# 08_STORE_SourceRegister.net
KiCad netlist of a schematic drawn in EAGLE
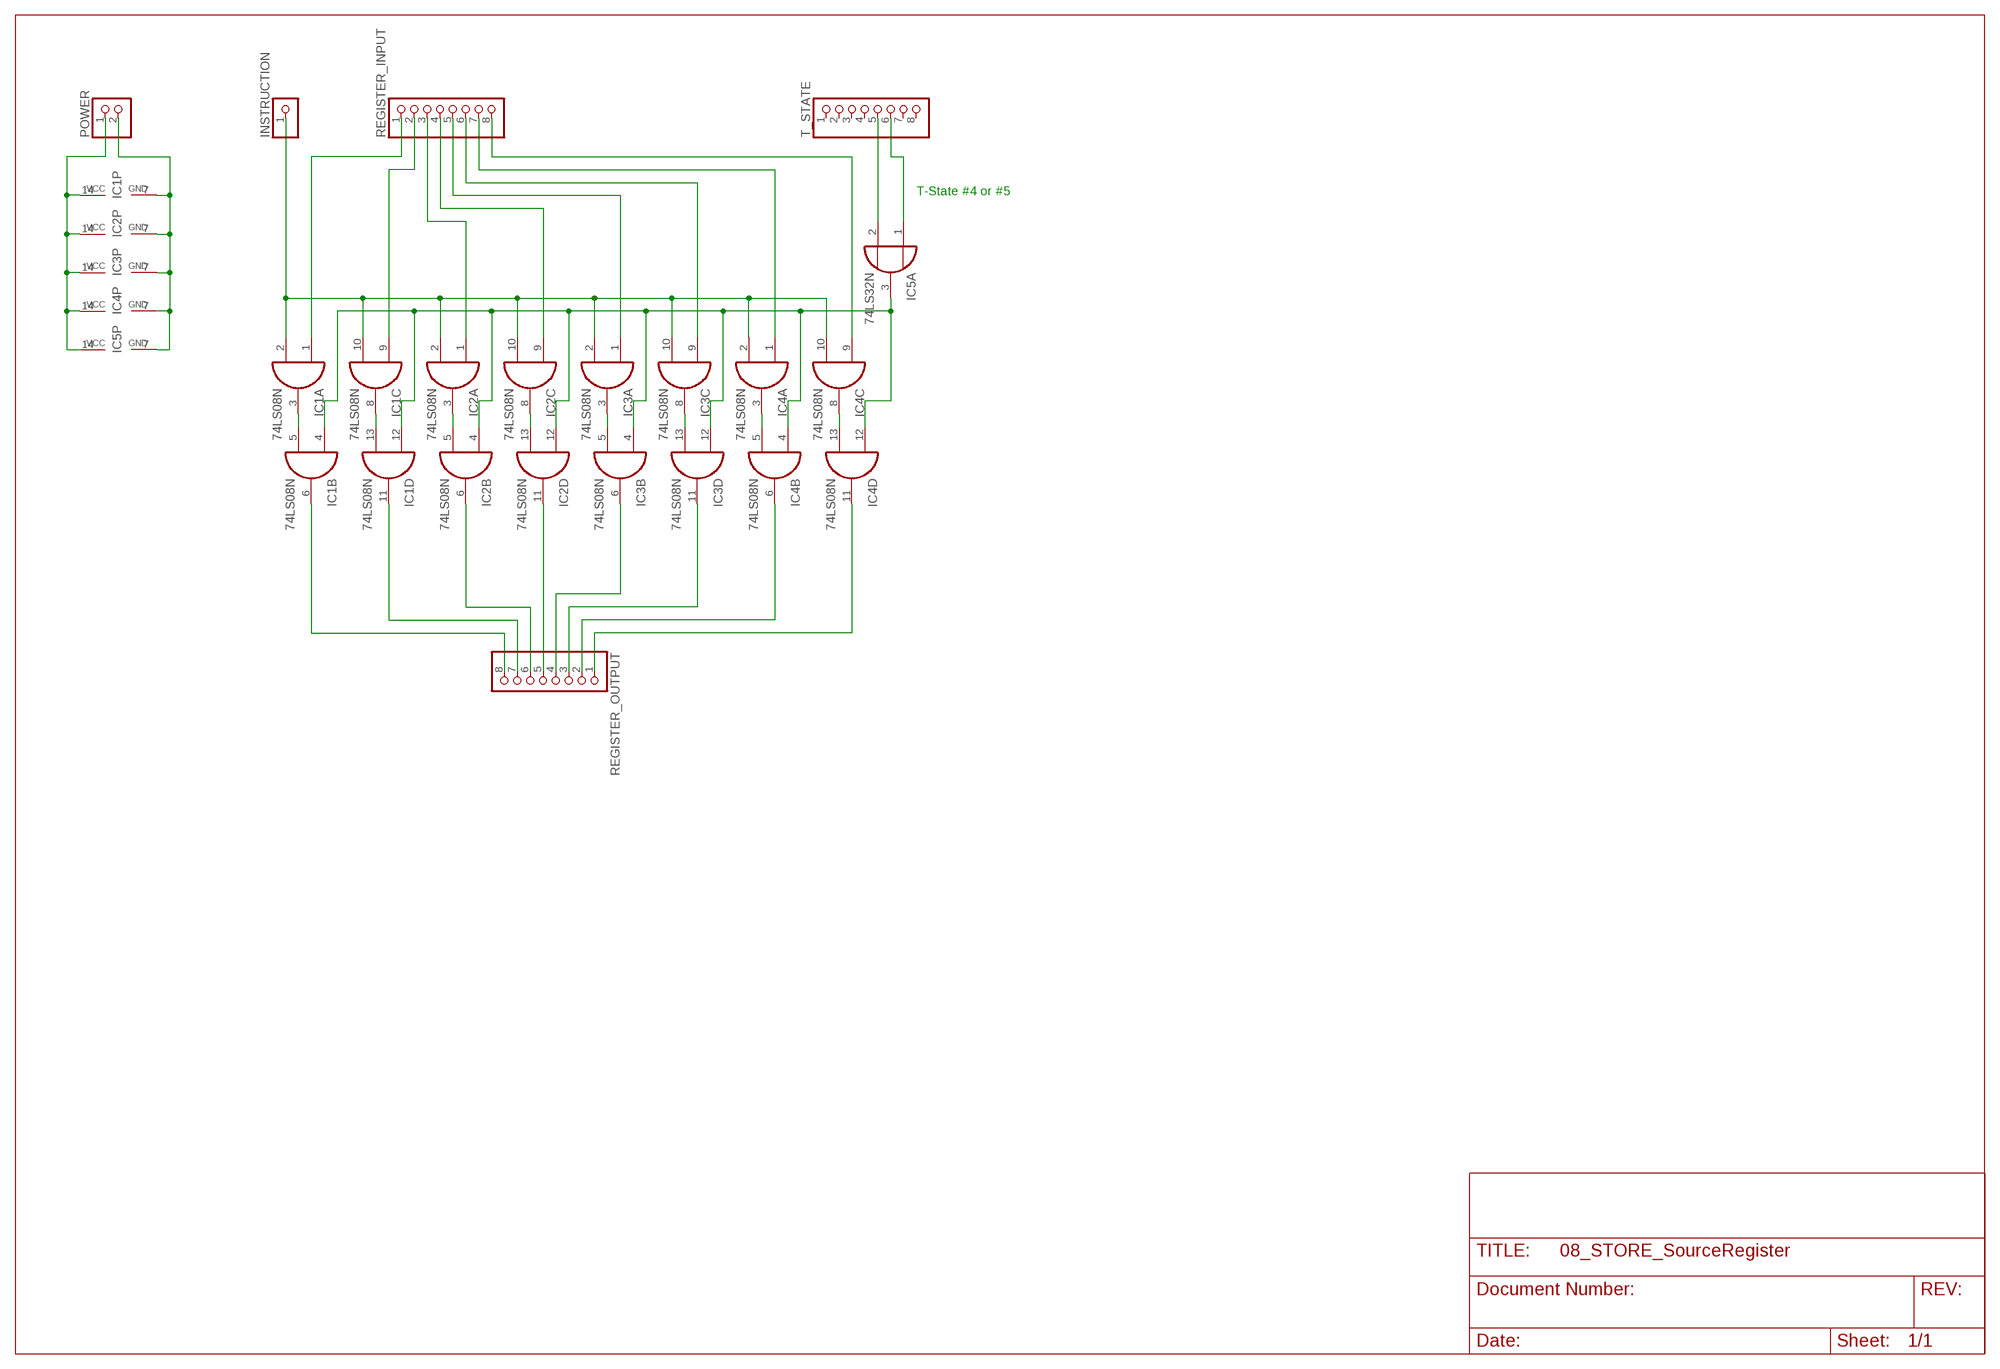
[diagram p0: schematic, sheet 1]

(export (version "E")
  (design (tool "Eeschema 10.0.6"))
  (components
    (comp (ref "IC1")
      (value "74LS08N")
      (footprint "eagle-import:DIL14")
      (libsource (lib "eagle-import") (part "7408NLS"))
    )
    (comp (ref "IC2")
      (value "74LS08N")
      (footprint "eagle-import:DIL14")
      (libsource (lib "eagle-import") (part "7408NLS"))
    )
    (comp (ref "IC3")
      (value "74LS08N")
      (footprint "eagle-import:DIL14")
      (libsource (lib "eagle-import") (part "7408NLS"))
    )
    (comp (ref "IC4")
      (value "74LS08N")
      (footprint "eagle-import:DIL14")
      (libsource (lib "eagle-import") (part "7408NLS"))
    )
    (comp (ref "IC5")
      (value "74LS32N")
      (footprint "eagle-import:DIL14")
      (libsource (lib "eagle-import") (part "7432NLS"))
    )
    (comp (ref "INSTRUCTION")
      (value "PINHD-1X1")
      (footprint "eagle-import:1X01")
      (libsource (lib "eagle-import") (part "PINHD-1X1"))
    )
    (comp (ref "POWER")
      (value "PINHD-1X2")
      (footprint "eagle-import:1X02")
      (libsource (lib "eagle-import") (part "PINHD-1X2"))
    )
    (comp (ref "REGISTER_INPUT")
      (value "PINHD-1X8")
      (footprint "eagle-import:1X08")
      (libsource (lib "eagle-import") (part "PINHD-1X8"))
    )
    (comp (ref "REGISTER_OUTPUT")
      (value "PINHD-1X8")
      (footprint "eagle-import:1X08")
      (libsource (lib "eagle-import") (part "PINHD-1X8"))
    )
    (comp (ref "T_STATE")
      (value "PINHD-1X8")
      (footprint "eagle-import:1X08")
      (libsource (lib "eagle-import") (part "PINHD-1X8"))
    )
  )
  (nets
    (net (code "1") (name "Net-(IC1A-I0)") (class "Default")
      (node (ref "IC1") (pin "1") (pinfunction "I0_1") (pintype "input"))
      (node (ref "REGISTER_INPUT") (pin "1") (pinfunction "1_1") (pintype "passive"))
    )
    (net (code "2") (name "Net-(IC1A-I1)") (class "Default")
      (node (ref "IC1") (pin "10") (pinfunction "I1_10") (pintype "input"))
      (node (ref "IC1") (pin "2") (pinfunction "I1_2") (pintype "input"))
      (node (ref "IC2") (pin "10") (pinfunction "I1_10") (pintype "input"))
      (node (ref "IC2") (pin "2") (pinfunction "I1_2") (pintype "input"))
      (node (ref "IC3") (pin "10") (pinfunction "I1_10") (pintype "input"))
      (node (ref "IC3") (pin "2") (pinfunction "I1_2") (pintype "input"))
      (node (ref "IC4") (pin "10") (pinfunction "I1_10") (pintype "input"))
      (node (ref "IC4") (pin "2") (pinfunction "I1_2") (pintype "input"))
      (node (ref "INSTRUCTION") (pin "1") (pinfunction "1_1") (pintype "passive"))
    )
    (net (code "3") (name "Net-(IC1A-O)") (class "Default")
      (node (ref "IC1") (pin "3") (pinfunction "O_3") (pintype "output"))
      (node (ref "IC1") (pin "5") (pinfunction "I1_5") (pintype "input"))
    )
    (net (code "4") (name "Net-(IC1B-I0)") (class "Default")
      (node (ref "IC1") (pin "12") (pinfunction "I0_12") (pintype "input"))
      (node (ref "IC1") (pin "4") (pinfunction "I0_4") (pintype "input"))
      (node (ref "IC2") (pin "12") (pinfunction "I0_12") (pintype "input"))
      (node (ref "IC2") (pin "4") (pinfunction "I0_4") (pintype "input"))
      (node (ref "IC3") (pin "12") (pinfunction "I0_12") (pintype "input"))
      (node (ref "IC3") (pin "4") (pinfunction "I0_4") (pintype "input"))
      (node (ref "IC4") (pin "12") (pinfunction "I0_12") (pintype "input"))
      (node (ref "IC4") (pin "4") (pinfunction "I0_4") (pintype "input"))
      (node (ref "IC5") (pin "3") (pinfunction "O_3") (pintype "output"))
    )
    (net (code "5") (name "Net-(IC1B-O)") (class "Default")
      (node (ref "IC1") (pin "6") (pinfunction "O_6") (pintype "output"))
      (node (ref "REGISTER_OUTPUT") (pin "8") (pinfunction "8_8") (pintype "passive"))
    )
    (net (code "6") (name "Net-(IC1C-I0)") (class "Default")
      (node (ref "IC1") (pin "9") (pinfunction "I0_9") (pintype "input"))
      (node (ref "REGISTER_INPUT") (pin "2") (pinfunction "2_2") (pintype "passive"))
    )
    (net (code "7") (name "Net-(IC1C-O)") (class "Default")
      (node (ref "IC1") (pin "13") (pinfunction "I1_13") (pintype "input"))
      (node (ref "IC1") (pin "8") (pinfunction "O_8") (pintype "output"))
    )
    (net (code "8") (name "Net-(IC1D-O)") (class "Default")
      (node (ref "IC1") (pin "11") (pinfunction "O_11") (pintype "output"))
      (node (ref "REGISTER_OUTPUT") (pin "7") (pinfunction "7_7") (pintype "passive"))
    )
    (net (code "9") (name "Net-(IC1E-GND)") (class "Default")
      (node (ref "IC1") (pin "7") (pinfunction "GND_7") (pintype "power_in"))
      (node (ref "IC2") (pin "7") (pinfunction "GND_7") (pintype "power_in"))
      (node (ref "IC3") (pin "7") (pinfunction "GND_7") (pintype "power_in"))
      (node (ref "IC4") (pin "7") (pinfunction "GND_7") (pintype "power_in"))
      (node (ref "IC5") (pin "7") (pinfunction "GND_7") (pintype "power_in"))
      (node (ref "POWER") (pin "2") (pinfunction "2_2") (pintype "passive"))
    )
    (net (code "10") (name "Net-(IC1E-VCC)") (class "Default")
      (node (ref "IC1") (pin "14") (pinfunction "VCC_14") (pintype "power_in"))
      (node (ref "IC2") (pin "14") (pinfunction "VCC_14") (pintype "power_in"))
      (node (ref "IC3") (pin "14") (pinfunction "VCC_14") (pintype "power_in"))
      (node (ref "IC4") (pin "14") (pinfunction "VCC_14") (pintype "power_in"))
      (node (ref "IC5") (pin "14") (pinfunction "VCC_14") (pintype "power_in"))
      (node (ref "POWER") (pin "1") (pinfunction "1_1") (pintype "passive"))
    )
    (net (code "11") (name "Net-(IC2A-I0)") (class "Default")
      (node (ref "IC2") (pin "1") (pinfunction "I0_1") (pintype "input"))
      (node (ref "REGISTER_INPUT") (pin "3") (pinfunction "3_3") (pintype "passive"))
    )
    (net (code "12") (name "Net-(IC2A-O)") (class "Default")
      (node (ref "IC2") (pin "3") (pinfunction "O_3") (pintype "output"))
      (node (ref "IC2") (pin "5") (pinfunction "I1_5") (pintype "input"))
    )
    (net (code "13") (name "Net-(IC2B-O)") (class "Default")
      (node (ref "IC2") (pin "6") (pinfunction "O_6") (pintype "output"))
      (node (ref "REGISTER_OUTPUT") (pin "6") (pinfunction "6_6") (pintype "passive"))
    )
    (net (code "14") (name "Net-(IC2C-I0)") (class "Default")
      (node (ref "IC2") (pin "9") (pinfunction "I0_9") (pintype "input"))
      (node (ref "REGISTER_INPUT") (pin "4") (pinfunction "4_4") (pintype "passive"))
    )
    (net (code "15") (name "Net-(IC2C-O)") (class "Default")
      (node (ref "IC2") (pin "13") (pinfunction "I1_13") (pintype "input"))
      (node (ref "IC2") (pin "8") (pinfunction "O_8") (pintype "output"))
    )
    (net (code "16") (name "Net-(IC2D-O)") (class "Default")
      (node (ref "IC2") (pin "11") (pinfunction "O_11") (pintype "output"))
      (node (ref "REGISTER_OUTPUT") (pin "5") (pinfunction "5_5") (pintype "passive"))
    )
    (net (code "17") (name "Net-(IC3A-I0)") (class "Default")
      (node (ref "IC3") (pin "1") (pinfunction "I0_1") (pintype "input"))
      (node (ref "REGISTER_INPUT") (pin "5") (pinfunction "5_5") (pintype "passive"))
    )
    (net (code "18") (name "Net-(IC3A-O)") (class "Default")
      (node (ref "IC3") (pin "3") (pinfunction "O_3") (pintype "output"))
      (node (ref "IC3") (pin "5") (pinfunction "I1_5") (pintype "input"))
    )
    (net (code "19") (name "Net-(IC3B-O)") (class "Default")
      (node (ref "IC3") (pin "6") (pinfunction "O_6") (pintype "output"))
      (node (ref "REGISTER_OUTPUT") (pin "4") (pinfunction "4_4") (pintype "passive"))
    )
    (net (code "20") (name "Net-(IC3C-I0)") (class "Default")
      (node (ref "IC3") (pin "9") (pinfunction "I0_9") (pintype "input"))
      (node (ref "REGISTER_INPUT") (pin "6") (pinfunction "6_6") (pintype "passive"))
    )
    (net (code "21") (name "Net-(IC3C-O)") (class "Default")
      (node (ref "IC3") (pin "13") (pinfunction "I1_13") (pintype "input"))
      (node (ref "IC3") (pin "8") (pinfunction "O_8") (pintype "output"))
    )
    (net (code "22") (name "Net-(IC3D-O)") (class "Default")
      (node (ref "IC3") (pin "11") (pinfunction "O_11") (pintype "output"))
      (node (ref "REGISTER_OUTPUT") (pin "3") (pinfunction "3_3") (pintype "passive"))
    )
    (net (code "23") (name "Net-(IC4A-I0)") (class "Default")
      (node (ref "IC4") (pin "1") (pinfunction "I0_1") (pintype "input"))
      (node (ref "REGISTER_INPUT") (pin "7") (pinfunction "7_7") (pintype "passive"))
    )
    (net (code "24") (name "Net-(IC4A-O)") (class "Default")
      (node (ref "IC4") (pin "3") (pinfunction "O_3") (pintype "output"))
      (node (ref "IC4") (pin "5") (pinfunction "I1_5") (pintype "input"))
    )
    (net (code "25") (name "Net-(IC4B-O)") (class "Default")
      (node (ref "IC4") (pin "6") (pinfunction "O_6") (pintype "output"))
      (node (ref "REGISTER_OUTPUT") (pin "2") (pinfunction "2_2") (pintype "passive"))
    )
    (net (code "26") (name "Net-(IC4C-I0)") (class "Default")
      (node (ref "IC4") (pin "9") (pinfunction "I0_9") (pintype "input"))
      (node (ref "REGISTER_INPUT") (pin "8") (pinfunction "8_8") (pintype "passive"))
    )
    (net (code "27") (name "Net-(IC4C-O)") (class "Default")
      (node (ref "IC4") (pin "13") (pinfunction "I1_13") (pintype "input"))
      (node (ref "IC4") (pin "8") (pinfunction "O_8") (pintype "output"))
    )
    (net (code "28") (name "Net-(IC4D-O)") (class "Default")
      (node (ref "IC4") (pin "11") (pinfunction "O_11") (pintype "output"))
      (node (ref "REGISTER_OUTPUT") (pin "1") (pinfunction "1_1") (pintype "passive"))
    )
    (net (code "29") (name "Net-(IC5A-I0)") (class "Default")
      (node (ref "IC5") (pin "1") (pinfunction "I0_1") (pintype "input"))
      (node (ref "T_STATE") (pin "6") (pinfunction "6_6") (pintype "passive"))
    )
    (net (code "30") (name "Net-(IC5A-I1)") (class "Default")
      (node (ref "IC5") (pin "2") (pinfunction "I1_2") (pintype "input"))
      (node (ref "T_STATE") (pin "5") (pinfunction "5_5") (pintype "passive"))
    )
    (net (code "31") (name "unconnected-(T_STATE-Pad1)") (class "Default")
      (node (ref "T_STATE") (pin "1") (pinfunction "1_1") (pintype "passive"))
    )
    (net (code "32") (name "unconnected-(T_STATE-Pad2)") (class "Default")
      (node (ref "T_STATE") (pin "2") (pinfunction "2_2") (pintype "passive"))
    )
    (net (code "33") (name "unconnected-(T_STATE-Pad3)") (class "Default")
      (node (ref "T_STATE") (pin "3") (pinfunction "3_3") (pintype "passive"))
    )
    (net (code "34") (name "unconnected-(T_STATE-Pad4)") (class "Default")
      (node (ref "T_STATE") (pin "4") (pinfunction "4_4") (pintype "passive"))
    )
    (net (code "35") (name "unconnected-(T_STATE-Pad7)") (class "Default")
      (node (ref "T_STATE") (pin "7") (pinfunction "7_7") (pintype "passive"))
    )
    (net (code "36") (name "unconnected-(T_STATE-Pad8)") (class "Default")
      (node (ref "T_STATE") (pin "8") (pinfunction "8_8") (pintype "passive"))
    )
  )
)
